# PRUC-Voltmeter_Local-Supply.net
KiCad netlist of a schematic drawn in Altium Designer
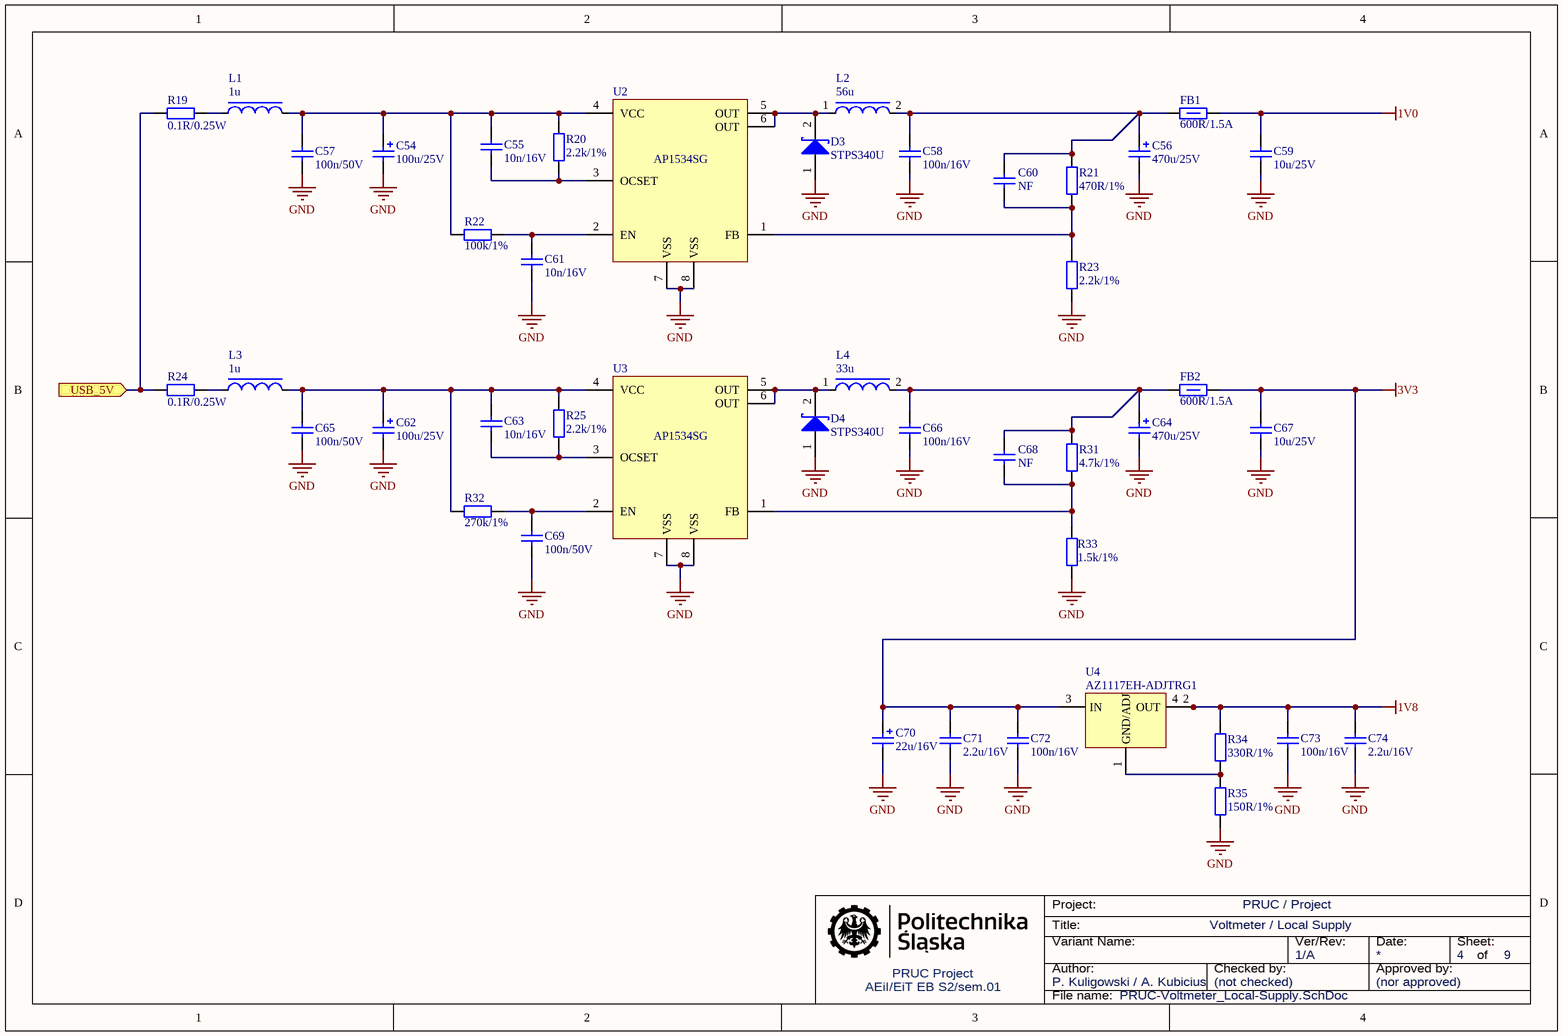
[diagram p0: PRUC-Voltmeter_Local-Supply.SchDoc]

(export (version "E")
  (design (tool "Eeschema 10.0.6"))
  (components
    (comp (ref "C54")
      (value "100u/25V")
      (footprint "E_Panasonic")
      (fields (field (name "PART NUMBER") "EEEFK1E101P") (field (name "MANUFACTURER") "Panasonic"))
      (libsource (lib "private") (part "Cap_Pol"))
    )
    (comp (ref "C55")
      (value "10n/16V")
      (footprint "MLCC_0603")
      (fields (field (name "PART NUMBER") "CL10B103KB8NNNC") (field (name "MANUFACTURER") "Samsung"))
      (libsource (lib "private") (part "Cap"))
    )
    (comp (ref "C56")
      (value "470u/25V")
      (footprint "G_Panasonic")
      (fields (field (name "PART NUMBER") "EEEFK1E471P") (field (name "MANUFACTURER") "Panasonic"))
      (libsource (lib "private") (part "Cap_Pol"))
    )
    (comp (ref "C57")
      (value "100n/50V")
      (footprint "MLCC_0805")
      (fields (field (name "PART NUMBER") "CL21B104JBCNNNC") (field (name "MANUFACTURER") "Samsung"))
      (libsource (lib "private") (part "Cap"))
    )
    (comp (ref "C58")
      (value "100n/16V")
      (footprint "MLCC_0603")
      (fields (field (name "PART NUMBER") "CL10B104KO8NNNC") (field (name "MANUFACTURER") "Samsung"))
      (libsource (lib "private") (part "Cap"))
    )
    (comp (ref "C59")
      (value "10u/25V")
      (footprint "MLCC_1206")
      (fields (field (name "PART NUMBER") "CL31B106KAHNNNE") (field (name "MANUFACTURER") "Samsung"))
      (libsource (lib "private") (part "Cap"))
    )
    (comp (ref "C60")
      (value "NF")
      (footprint "MLCC_0603")
      (fields (field (name "PART NUMBER") "CL10C100JB8NNNC") (field (name "MANUFACTURER") "Samsung"))
      (libsource (lib "private") (part "Cap"))
    )
    (comp (ref "C61")
      (value "10n/16V")
      (footprint "MLCC_0603")
      (fields (field (name "PART NUMBER") "CL10B103KB8NNNC") (field (name "MANUFACTURER") "Samsung"))
      (libsource (lib "private") (part "Cap"))
    )
    (comp (ref "C62")
      (value "100u/25V")
      (footprint "E_Panasonic")
      (fields (field (name "PART NUMBER") "EEEFK1E101P") (field (name "MANUFACTURER") "Panasonic"))
      (libsource (lib "private") (part "Cap_Pol"))
    )
    (comp (ref "C63")
      (value "10n/16V")
      (footprint "MLCC_0603")
      (fields (field (name "PART NUMBER") "CL10B103KB8NNNC") (field (name "MANUFACTURER") "Samsung"))
      (libsource (lib "private") (part "Cap"))
    )
    (comp (ref "C64")
      (value "470u/25V")
      (footprint "G_Panasonic")
      (fields (field (name "PART NUMBER") "EEEFK1E471P") (field (name "MANUFACTURER") "Panasonic"))
      (libsource (lib "private") (part "Cap_Pol"))
    )
    (comp (ref "C65")
      (value "100n/50V")
      (footprint "MLCC_0805")
      (fields (field (name "PART NUMBER") "CL21B104JBCNNNC") (field (name "MANUFACTURER") "Samsung"))
      (libsource (lib "private") (part "Cap"))
    )
    (comp (ref "C66")
      (value "100n/16V")
      (footprint "MLCC_0603")
      (fields (field (name "PART NUMBER") "CL10B104KO8NNNC") (field (name "MANUFACTURER") "Samsung"))
      (libsource (lib "private") (part "Cap"))
    )
    (comp (ref "C67")
      (value "10u/25V")
      (footprint "MLCC_1206")
      (fields (field (name "PART NUMBER") "CL31B106KAHNNNE") (field (name "MANUFACTURER") "Samsung"))
      (libsource (lib "private") (part "Cap"))
    )
    (comp (ref "C68")
      (value "NF")
      (footprint "MLCC_0603")
      (fields (field (name "PART NUMBER") "CL10C100JB8NNNC") (field (name "MANUFACTURER") "Samsung"))
      (libsource (lib "private") (part "Cap"))
    )
    (comp (ref "C69")
      (value "100n/50V")
      (footprint "MLCC_0805")
      (fields (field (name "PART NUMBER") "CL21B104JBCNNNC") (field (name "MANUFACTURER") "Samsung"))
      (libsource (lib "private") (part "Cap"))
    )
    (comp (ref "C70")
      (value "22u/16V")
      (footprint "Tantalum_B")
      (fields
        (field (name "PART NUMBER") "TAJB226K016R")
        (field (name "MANUFACTURER") "AVX")
        (field (name "MANUFACTURER PART NUMBER") "TAJB226K016RNJ")
      )
      (libsource (lib "kplabs") (part "Cap_Pol"))
    )
    (comp (ref "C71")
      (value "2.2u/16V")
      (footprint "MLCC_0603")
      (fields (field (name "PART NUMBER") "CL10A225KO8NNNC") (field (name "MANUFACTURER") "Samsung"))
      (libsource (lib "kplabs") (part "Cap"))
    )
    (comp (ref "C72")
      (value "100n/16V")
      (footprint "MLCC_0603")
      (fields (field (name "PART NUMBER") "CL10B104KO8NNNC") (field (name "MANUFACTURER") "Samsung"))
      (libsource (lib "kplabs") (part "Cap"))
    )
    (comp (ref "C73")
      (value "100n/16V")
      (footprint "MLCC_0603")
      (fields (field (name "PART NUMBER") "CL10B104KO8NNNC") (field (name "MANUFACTURER") "Samsung"))
      (libsource (lib "kplabs") (part "Cap"))
    )
    (comp (ref "C74")
      (value "2.2u/16V")
      (footprint "MLCC_0603")
      (fields (field (name "PART NUMBER") "CL10A225KO8NNNC") (field (name "MANUFACTURER") "Samsung"))
      (libsource (lib "kplabs") (part "Cap"))
    )
    (comp (ref "D3")
      (value "STPS340U")
      (footprint "DO-214AA")
      (fields (field (name "MANUFACTURER") "ST"))
      (libsource (lib "private") (part "Schottky_AK"))
    )
    (comp (ref "D4")
      (value "STPS340U")
      (footprint "DO-214AA")
      (fields (field (name "MANUFACTURER") "ST"))
      (libsource (lib "private") (part "Schottky_AK"))
    )
    (comp (ref "FB1")
      (value "600R/1.5A")
      (footprint "FerriteBead_1206")
      (fields (field (name "PART NUMBER") "BLM31PG601SN1L") (field (name "MANUFACTURER") "Murata"))
      (libsource (lib "private") (part "FerriteBead"))
    )
    (comp (ref "FB2")
      (value "600R/1.5A")
      (footprint "FerriteBead_1206")
      (fields (field (name "PART NUMBER") "BLM31PG601SN1L") (field (name "MANUFACTURER") "Murata"))
      (libsource (lib "private") (part "FerriteBead"))
    )
    (comp (ref "L1")
      (value "1u")
      (footprint "DER0705")
      (fields (field (name "PART NUMBER") "DER0705-1") (field (name "MANUFACTURER") "Ferrocore"))
      (libsource (lib "private") (part "Inductor"))
    )
    (comp (ref "L2")
      (value "56u")
      (footprint "DE1207")
      (fields (field (name "PART NUMBER") "DE1207-56") (field (name "MANUFACTURER") "Ferrocore"))
      (libsource (lib "kplabs") (part "Inductor"))
    )
    (comp (ref "L3")
      (value "1u")
      (footprint "DER0705")
      (fields (field (name "PART NUMBER") "DER0705-1") (field (name "MANUFACTURER") "Ferrocore"))
      (libsource (lib "private") (part "Inductor"))
    )
    (comp (ref "L4")
      (value "33u")
      (footprint "DE1205")
      (fields (field (name "PART NUMBER") "DE1205-33") (field (name "MANUFACTURER") "Ferrocore"))
      (libsource (lib "kplabs") (part "Inductor"))
    )
    (comp (ref "R19")
      (value "0.1R/0.25W")
      (footprint "R_1206")
      (fields (field (name "PART NUMBER") "1206S4J010KT5E") (field (name "MANUFACTURER") "Royalohm"))
      (libsource (lib "") (part "Res_1"))
    )
    (comp (ref "R20")
      (value "2.2k/1%")
      (footprint "R_0603")
      (fields (field (name "PART NUMBER") "0603SAF2201T5E") (field (name "MANUFACTURER") "Royalohm"))
      (libsource (lib "private") (part "Res"))
    )
    (comp (ref "R21")
      (value "470R/1%")
      (footprint "R_0603")
      (fields (field (name "PART NUMBER") "0603SAF4700T5E") (field (name "MANUFACTURER") "Royalohm"))
      (libsource (lib "kplabs") (part "Res"))
    )
    (comp (ref "R22")
      (value "100k/1%")
      (footprint "R_0603")
      (fields (field (name "PART NUMBER") "0603SAF1003T5E") (field (name "MANUFACTURER") "Royalohm"))
      (libsource (lib "") (part "Res_1"))
    )
    (comp (ref "R23")
      (value "2.2k/1%")
      (footprint "R_0603")
      (fields (field (name "PART NUMBER") "0603SAF2201T5E") (field (name "MANUFACTURER") "Royalohm"))
      (libsource (lib "kplabs") (part "Res"))
    )
    (comp (ref "R24")
      (value "0.1R/0.25W")
      (footprint "R_1206")
      (fields (field (name "PART NUMBER") "1206S4J010KT5E") (field (name "MANUFACTURER") "Royalohm"))
      (libsource (lib "") (part "Res_1"))
    )
    (comp (ref "R25")
      (value "2.2k/1%")
      (footprint "R_0603")
      (fields (field (name "PART NUMBER") "0603SAF2201T5E") (field (name "MANUFACTURER") "Royalohm"))
      (libsource (lib "private") (part "Res"))
    )
    (comp (ref "R31")
      (value "4.7k/1%")
      (footprint "R_0603")
      (fields
        (field (name "PART NUMBER") "0603SAF4701T5E")
        (field (name "MANUFACTURER") "Royalohm")
        (field (name "MANUFACTURER PART NUMBER") "SMD0603-4K7-1%")
      )
      (libsource (lib "kplabs") (part "Res"))
    )
    (comp (ref "R32")
      (value "270k/1%")
      (footprint "R_0603")
      (fields (field (name "PART NUMBER") "CRCW0603270KFKTABC") (field (name "MANUFACTURER") "Vishay"))
      (libsource (lib "") (part "Res_1"))
    )
    (comp (ref "R33")
      (value "1.5k/1%")
      (footprint "R_0603")
      (fields
        (field (name "PART NUMBER") "0603SAF1501T5E")
        (field (name "MANUFACTURER") "Royalohm")
        (field (name "MANUFACTURER PART NUMBER") "SMD0603-1K5-1%")
      )
      (libsource (lib "private") (part "Res"))
    )
    (comp (ref "R34")
      (value "330R/1%")
      (footprint "R_0603")
      (fields (field (name "PART NUMBER") "0603SAF3300T5E") (field (name "MANUFACTURER") "Royalohm"))
      (libsource (lib "kplabs") (part "Res"))
    )
    (comp (ref "R35")
      (value "150R/1%")
      (footprint "R_0603")
      (fields (field (name "PART NUMBER") "0603SAF1500T5E") (field (name "MANUFACTURER") "Royalohm"))
      (libsource (lib "kplabs") (part "Res"))
    )
    (comp (ref "U2")
      (value "AP1534SG")
      (footprint "SOIC-8-N")
      (fields
        (field (name "MANUFACTURER") "Diodes Incorporated")
        (field (name "MANUFACTURER PART NUMBER") "AP1534SG-13")
      )
      (libsource (lib "private") (part "AP1534SG"))
    )
    (comp (ref "U3")
      (value "AP1534SG")
      (footprint "SOIC-8-N")
      (fields
        (field (name "MANUFACTURER") "Diodes Incorporated")
        (field (name "MANUFACTURER PART NUMBER") "AP1534SG-13")
      )
      (libsource (lib "private") (part "AP1534SG"))
    )
    (comp (ref "U4")
      (value "AZ1117EH-ADJTRG1")
      (footprint "SOT223")
      (fields (field (name "MANUFACTURER") "Diodes Incorporated"))
      (libsource (lib "kplabs") (part "AZ1117EH-ADJ"))
    )
  )
  (nets
    (net (code "1") (name "/USB_5V") (class "Default")
      (node (ref "R19") (pin "1") (pinfunction "1_1") (pintype "passive"))
      (node (ref "R24") (pin "1") (pinfunction "1_1") (pintype "passive"))
    )
    (net (code "2") (name "1V0") (class "Default")
      (node (ref "C59") (pin "1") (pinfunction "1_1") (pintype "passive"))
      (node (ref "FB1") (pin "1") (pinfunction "1_1") (pintype "passive"))
    )
    (net (code "3") (name "1V8") (class "Default")
      (node (ref "C73") (pin "1") (pinfunction "1_1") (pintype "passive"))
      (node (ref "C74") (pin "1") (pinfunction "1_1") (pintype "passive"))
      (node (ref "R34") (pin "1") (pinfunction "1_1") (pintype "passive"))
      (node (ref "U4") (pin "2") (pinfunction "GND_2") (pintype "power_in"))
      (node (ref "U4") (pin "4") (pinfunction "OUT_4") (pintype "power_in"))
    )
    (net (code "4") (name "3V3") (class "Default")
      (node (ref "C67") (pin "1") (pinfunction "1_1") (pintype "passive"))
      (node (ref "C70") (pin "1") (pinfunction "1_1") (pintype "passive"))
      (node (ref "C71") (pin "1") (pinfunction "1_1") (pintype "passive"))
      (node (ref "C72") (pin "1") (pinfunction "1_1") (pintype "passive"))
      (node (ref "FB2") (pin "1") (pinfunction "1_1") (pintype "passive"))
      (node (ref "U4") (pin "3") (pinfunction "IN_3") (pintype "power_in"))
    )
    (net (code "5") (name "GND") (class "Default")
      (node (ref "C54") (pin "2") (pinfunction "2_2") (pintype "passive"))
      (node (ref "C56") (pin "2") (pinfunction "2_2") (pintype "passive"))
      (node (ref "C57") (pin "2") (pinfunction "2_2") (pintype "passive"))
      (node (ref "C58") (pin "2") (pinfunction "2_2") (pintype "passive"))
      (node (ref "C59") (pin "2") (pinfunction "2_2") (pintype "passive"))
      (node (ref "C61") (pin "2") (pinfunction "2_2") (pintype "passive"))
      (node (ref "C62") (pin "2") (pinfunction "2_2") (pintype "passive"))
      (node (ref "C64") (pin "2") (pinfunction "2_2") (pintype "passive"))
      (node (ref "C65") (pin "2") (pinfunction "2_2") (pintype "passive"))
      (node (ref "C66") (pin "2") (pinfunction "2_2") (pintype "passive"))
      (node (ref "C67") (pin "2") (pinfunction "2_2") (pintype "passive"))
      (node (ref "C69") (pin "2") (pinfunction "2_2") (pintype "passive"))
      (node (ref "C70") (pin "2") (pinfunction "2_2") (pintype "passive"))
      (node (ref "C71") (pin "2") (pinfunction "2_2") (pintype "passive"))
      (node (ref "C72") (pin "2") (pinfunction "2_2") (pintype "passive"))
      (node (ref "C73") (pin "2") (pinfunction "2_2") (pintype "passive"))
      (node (ref "C74") (pin "2") (pinfunction "2_2") (pintype "passive"))
      (node (ref "D3") (pin "1") (pinfunction "A_1") (pintype "passive"))
      (node (ref "D4") (pin "1") (pinfunction "A_1") (pintype "passive"))
      (node (ref "R23") (pin "2") (pinfunction "2_2") (pintype "passive"))
      (node (ref "R33") (pin "2") (pinfunction "2_2") (pintype "passive"))
      (node (ref "R35") (pin "2") (pinfunction "2_2") (pintype "passive"))
      (node (ref "U2") (pin "7") (pinfunction "VSS_7") (pintype "passive"))
      (node (ref "U2") (pin "8") (pinfunction "VSS_8") (pintype "passive"))
      (node (ref "U3") (pin "7") (pinfunction "VSS_7") (pintype "passive"))
      (node (ref "U3") (pin "8") (pinfunction "VSS_8") (pintype "passive"))
    )
    (net (code "6") (name "Net-(C56-Pad1)") (class "Default")
      (node (ref "C56") (pin "1") (pinfunction "1_1") (pintype "passive"))
      (node (ref "C58") (pin "1") (pinfunction "1_1") (pintype "passive"))
      (node (ref "C60") (pin "1") (pinfunction "1_1") (pintype "passive"))
      (node (ref "FB1") (pin "2") (pinfunction "2_2") (pintype "passive"))
      (node (ref "L2") (pin "2") (pinfunction "2_2") (pintype "passive"))
      (node (ref "R21") (pin "1") (pinfunction "1_1") (pintype "passive"))
    )
    (net (code "7") (name "Net-(C64-Pad1)") (class "Default")
      (node (ref "C64") (pin "1") (pinfunction "1_1") (pintype "passive"))
      (node (ref "C66") (pin "1") (pinfunction "1_1") (pintype "passive"))
      (node (ref "C68") (pin "1") (pinfunction "1_1") (pintype "passive"))
      (node (ref "FB2") (pin "2") (pinfunction "2_2") (pintype "passive"))
      (node (ref "L4") (pin "2") (pinfunction "2_2") (pintype "passive"))
      (node (ref "R31") (pin "1") (pinfunction "1_1") (pintype "passive"))
    )
    (net (code "8") (name "Net-(D3-K)") (class "Default")
      (node (ref "D3") (pin "2") (pinfunction "K_2") (pintype "passive"))
      (node (ref "L2") (pin "1") (pinfunction "1_1") (pintype "passive"))
      (node (ref "U2") (pin "5") (pinfunction "OUT_5") (pintype "passive"))
      (node (ref "U2") (pin "6") (pinfunction "OUT_6") (pintype "passive"))
    )
    (net (code "9") (name "Net-(D4-K)") (class "Default")
      (node (ref "D4") (pin "2") (pinfunction "K_2") (pintype "passive"))
      (node (ref "L4") (pin "1") (pinfunction "1_1") (pintype "passive"))
      (node (ref "U3") (pin "5") (pinfunction "OUT_5") (pintype "passive"))
      (node (ref "U3") (pin "6") (pinfunction "OUT_6") (pintype "passive"))
    )
    (net (code "10") (name "Net-(L1-Pad1)") (class "Default")
      (node (ref "L1") (pin "1") (pinfunction "1_1") (pintype "passive"))
      (node (ref "R19") (pin "2") (pinfunction "2_2") (pintype "passive"))
    )
    (net (code "11") (name "Net-(L3-Pad1)") (class "Default")
      (node (ref "L3") (pin "1") (pinfunction "1_1") (pintype "passive"))
      (node (ref "R24") (pin "2") (pinfunction "2_2") (pintype "passive"))
    )
    (net (code "12") (name "Net-(U2-EN)") (class "Default")
      (node (ref "C61") (pin "1") (pinfunction "1_1") (pintype "passive"))
      (node (ref "R22") (pin "2") (pinfunction "2_2") (pintype "passive"))
      (node (ref "U2") (pin "2") (pinfunction "EN_2") (pintype "passive"))
    )
    (net (code "13") (name "Net-(U2-FB)") (class "Default")
      (node (ref "C60") (pin "2") (pinfunction "2_2") (pintype "passive"))
      (node (ref "R21") (pin "2") (pinfunction "2_2") (pintype "passive"))
      (node (ref "R23") (pin "1") (pinfunction "1_1") (pintype "passive"))
      (node (ref "U2") (pin "1") (pinfunction "FB_1") (pintype "passive"))
    )
    (net (code "14") (name "Net-(U2-OCSET)") (class "Default")
      (node (ref "C55") (pin "2") (pinfunction "2_2") (pintype "passive"))
      (node (ref "R20") (pin "2") (pinfunction "2_2") (pintype "passive"))
      (node (ref "U2") (pin "3") (pinfunction "OCSET_3") (pintype "passive"))
    )
    (net (code "15") (name "Net-(U2-VCC)") (class "Default")
      (node (ref "C54") (pin "1") (pinfunction "1_1") (pintype "passive"))
      (node (ref "C55") (pin "1") (pinfunction "1_1") (pintype "passive"))
      (node (ref "C57") (pin "1") (pinfunction "1_1") (pintype "passive"))
      (node (ref "L1") (pin "2") (pinfunction "2_2") (pintype "passive"))
      (node (ref "R20") (pin "1") (pinfunction "1_1") (pintype "passive"))
      (node (ref "R22") (pin "1") (pinfunction "1_1") (pintype "passive"))
      (node (ref "U2") (pin "4") (pinfunction "VCC_4") (pintype "passive"))
    )
    (net (code "16") (name "Net-(U3-EN)") (class "Default")
      (node (ref "C69") (pin "1") (pinfunction "1_1") (pintype "passive"))
      (node (ref "R32") (pin "2") (pinfunction "2_2") (pintype "passive"))
      (node (ref "U3") (pin "2") (pinfunction "EN_2") (pintype "passive"))
    )
    (net (code "17") (name "Net-(U3-FB)") (class "Default")
      (node (ref "C68") (pin "2") (pinfunction "2_2") (pintype "passive"))
      (node (ref "R31") (pin "2") (pinfunction "2_2") (pintype "passive"))
      (node (ref "R33") (pin "1") (pinfunction "1_1") (pintype "passive"))
      (node (ref "U3") (pin "1") (pinfunction "FB_1") (pintype "passive"))
    )
    (net (code "18") (name "Net-(U3-OCSET)") (class "Default")
      (node (ref "C63") (pin "2") (pinfunction "2_2") (pintype "passive"))
      (node (ref "R25") (pin "2") (pinfunction "2_2") (pintype "passive"))
      (node (ref "U3") (pin "3") (pinfunction "OCSET_3") (pintype "passive"))
    )
    (net (code "19") (name "Net-(U3-VCC)") (class "Default")
      (node (ref "C62") (pin "1") (pinfunction "1_1") (pintype "passive"))
      (node (ref "C63") (pin "1") (pinfunction "1_1") (pintype "passive"))
      (node (ref "C65") (pin "1") (pinfunction "1_1") (pintype "passive"))
      (node (ref "L3") (pin "2") (pinfunction "2_2") (pintype "passive"))
      (node (ref "R25") (pin "1") (pinfunction "1_1") (pintype "passive"))
      (node (ref "R32") (pin "1") (pinfunction "1_1") (pintype "passive"))
      (node (ref "U3") (pin "4") (pinfunction "VCC_4") (pintype "passive"))
    )
    (net (code "20") (name "Net-(U4-GND{slash}ADJ)") (class "Default")
      (node (ref "R34") (pin "2") (pinfunction "2_2") (pintype "passive"))
      (node (ref "R35") (pin "1") (pinfunction "1_1") (pintype "passive"))
      (node (ref "U4") (pin "1") (pinfunction "GND/ADJ_1") (pintype "power_in"))
    )
  )
)
